# IOpins.net
KiCad netlist of a schematic drawn in Altium Designer
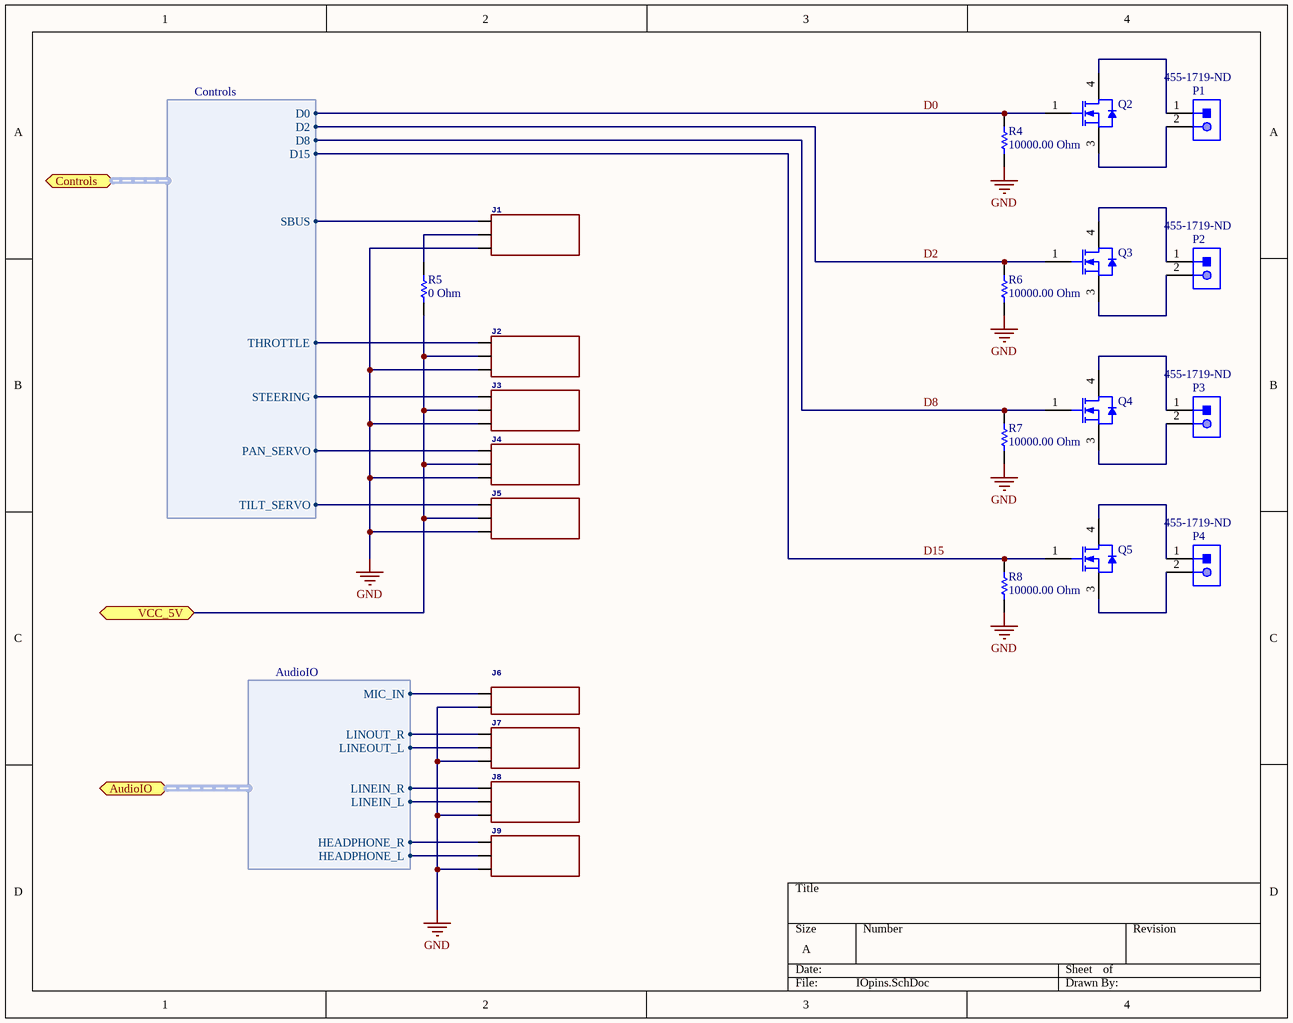
[diagram p0: IOpins.SchDoc]

(export (version "E")
  (design (tool "Eeschema 10.0.6"))
  (components
    (comp (ref "J1")
      (value "Library:  MF_Connectors Description: Header Connector with 03 Positions and 01 Rows. Use the LABEL Attribute to label the pin on the schematic and PCB. You can remove the attributes on the PCB by using the SMASH function on the part and then deleting the text.")
      (footprint "PTH_2.54MM_01X03")
      (fields (field (name "HOUSEPART") "YES") (field (name "MPN") "MF-CON-2.54mm-01x03"))
      (libsource (lib "MF_Connectors") (part "CON_01X03_PTH_2.54MM"))
    )
    (comp (ref "J2")
      (value "Library:  MF_Connectors Description: Header Connector with 03 Positions and 01 Rows. Use the LABEL Attribute to label the pin on the schematic and PCB. You can remove the attributes on the PCB by using the SMASH function on the part and then deleting the text.")
      (footprint "PTH_2.54MM_01X03")
      (fields (field (name "HOUSEPART") "YES") (field (name "MPN") "MF-CON-2.54mm-01x03"))
      (libsource (lib "MF_Connectors") (part "CON_01X03_PTH_2.54MM"))
    )
    (comp (ref "J3")
      (value "Library:  MF_Connectors Description: Header Connector with 03 Positions and 01 Rows. Use the LABEL Attribute to label the pin on the schematic and PCB. You can remove the attributes on the PCB by using the SMASH function on the part and then deleting the text.")
      (footprint "PTH_2.54MM_01X03")
      (fields (field (name "HOUSEPART") "YES") (field (name "MPN") "MF-CON-2.54mm-01x03"))
      (libsource (lib "MF_Connectors") (part "CON_01X03_PTH_2.54MM"))
    )
    (comp (ref "J4")
      (value "Library:  MF_Connectors Description: Header Connector with 03 Positions and 01 Rows. Use the LABEL Attribute to label the pin on the schematic and PCB. You can remove the attributes on the PCB by using the SMASH function on the part and then deleting the text.")
      (footprint "PTH_2.54MM_01X03")
      (fields (field (name "HOUSEPART") "YES") (field (name "MPN") "MF-CON-2.54mm-01x03"))
      (libsource (lib "MF_Connectors") (part "CON_01X03_PTH_2.54MM"))
    )
    (comp (ref "J5")
      (value "Library:  MF_Connectors Description: Header Connector with 03 Positions and 01 Rows. Use the LABEL Attribute to label the pin on the schematic and PCB. You can remove the attributes on the PCB by using the SMASH function on the part and then deleting the text.")
      (footprint "PTH_2.54MM_01X03")
      (fields (field (name "HOUSEPART") "YES") (field (name "MPN") "MF-CON-2.54mm-01x03"))
      (libsource (lib "MF_Connectors") (part "CON_01X03_PTH_2.54MM"))
    )
    (comp (ref "J6")
      (value "Library:  MF_Connectors Description: Header Connector with 02 Positions and 01 Rows. Use the LABEL Attribute to label the pin on the schematic and PCB. You can remove the attributes on the PCB by using the SMASH function on the part and then deleting the text.")
      (footprint "PTH_2.54MM_01X02")
      (fields (field (name "HOUSEPART") "YES") (field (name "MPN") "MF-CON-2.54mm-01x02"))
      (libsource (lib "MF_Connectors") (part "CON_01X02_PTH_2.54MM"))
    )
    (comp (ref "J7")
      (value "Library:  MF_Connectors Description: Header Connector with 03 Positions and 01 Rows. Use the LABEL Attribute to label the pin on the schematic and PCB. You can remove the attributes on the PCB by using the SMASH function on the part and then deleting the text.")
      (footprint "PTH_2.54MM_01X03")
      (fields (field (name "HOUSEPART") "YES") (field (name "MPN") "MF-CON-2.54mm-01x03"))
      (libsource (lib "MF_Connectors") (part "CON_01X03_PTH_2.54MM"))
    )
    (comp (ref "J8")
      (value "Library:  MF_Connectors Description: Header Connector with 03 Positions and 01 Rows. Use the LABEL Attribute to label the pin on the schematic and PCB. You can remove the attributes on the PCB by using the SMASH function on the part and then deleting the text.")
      (footprint "PTH_2.54MM_01X03")
      (fields (field (name "HOUSEPART") "YES") (field (name "MPN") "MF-CON-2.54mm-01x03"))
      (libsource (lib "MF_Connectors") (part "CON_01X03_PTH_2.54MM"))
    )
    (comp (ref "J9")
      (value "Library:  MF_Connectors Description: Header Connector with 03 Positions and 01 Rows. Use the LABEL Attribute to label the pin on the schematic and PCB. You can remove the attributes on the PCB by using the SMASH function on the part and then deleting the text.")
      (footprint "PTH_2.54MM_01X03")
      (fields (field (name "HOUSEPART") "YES") (field (name "MPN") "MF-CON-2.54mm-01x03"))
      (libsource (lib "MF_Connectors") (part "CON_01X03_PTH_2.54MM"))
    )
    (comp (ref "P1")
      (value "S2B-PH-K-S(LF)(SN)")
      (footprint "JST-S2B-PH-K-S_V")
      (fields (field (name "TOLERANCE") "20%") (field (name "SUPPLIER PART NUMBER 1") "455-1719-ND"))
      (libsource (lib "Altium Content Vault") (part "CMP-1755-00004-1"))
    )
    (comp (ref "P2")
      (value "S2B-PH-K-S(LF)(SN)")
      (footprint "JST-S2B-PH-K-S_V")
      (fields (field (name "TOLERANCE") "20%") (field (name "SUPPLIER PART NUMBER 1") "455-1719-ND"))
      (libsource (lib "Altium Content Vault") (part "CMP-1755-00004-1"))
    )
    (comp (ref "P3")
      (value "S2B-PH-K-S(LF)(SN)")
      (footprint "JST-S2B-PH-K-S_V")
      (fields (field (name "TOLERANCE") "20%") (field (name "SUPPLIER PART NUMBER 1") "455-1719-ND"))
      (libsource (lib "Altium Content Vault") (part "CMP-1755-00004-1"))
    )
    (comp (ref "P4")
      (value "S2B-PH-K-S(LF)(SN)")
      (footprint "JST-S2B-PH-K-S_V")
      (fields (field (name "TOLERANCE") "20%") (field (name "SUPPLIER PART NUMBER 1") "455-1719-ND"))
      (libsource (lib "Altium Content Vault") (part "CMP-1755-00004-1"))
    )
    (comp (ref "Q2")
      (value "NTD5867NLT4G")
      (footprint "ONSC-DPAK-3-369AA-01_V")
      (description "N-Channel Power MOSFET, 60 V, 20 A, 39 mOhm, 3-Pin DPAK, Pb-Free, Tape and Reel")
      (fields (field (name "MANUFACTURER") "On Semiconductor"))
      (libsource (lib "Altium Content Vault") (part "CMP-1058-00318-1"))
    )
    (comp (ref "Q3")
      (value "NTD5867NLT4G")
      (footprint "ONSC-DPAK-3-369AA-01_V")
      (description "N-Channel Power MOSFET, 60 V, 20 A, 39 mOhm, 3-Pin DPAK, Pb-Free, Tape and Reel")
      (fields (field (name "MANUFACTURER") "On Semiconductor"))
      (libsource (lib "Altium Content Vault") (part "CMP-1058-00318-1"))
    )
    (comp (ref "Q4")
      (value "NTD5867NLT4G")
      (footprint "ONSC-DPAK-3-369AA-01_V")
      (description "N-Channel Power MOSFET, 60 V, 20 A, 39 mOhm, 3-Pin DPAK, Pb-Free, Tape and Reel")
      (fields (field (name "MANUFACTURER") "On Semiconductor"))
      (libsource (lib "Altium Content Vault") (part "CMP-1058-00318-1"))
    )
    (comp (ref "Q5")
      (value "NTD5867NLT4G")
      (footprint "ONSC-DPAK-3-369AA-01_V")
      (description "N-Channel Power MOSFET, 60 V, 20 A, 39 mOhm, 3-Pin DPAK, Pb-Free, Tape and Reel")
      (fields (field (name "MANUFACTURER") "On Semiconductor"))
      (libsource (lib "Altium Content Vault") (part "CMP-1058-00318-1"))
    )
    (comp (ref "R4")
      (value "10000.00 Ohm")
      (footprint "RESC0402(1005)_N")
      (description "10K 0.063W 5% 0402 (1005 Metric)  SMD")
      (fields (field (name "POWER") "0.063 W") (field (name "TOLERANCE") "5 %"))
      (libsource (lib "Altium Content Vault") (part "CMP-1011-00081-1"))
    )
    (comp (ref "R5")
      (value "0 Ohm")
      (footprint "RESC0402(1005)_N")
      (description "10K 0.063W 5% 0402 (1005 Metric)  SMD")
      (fields (field (name "POWER") "0.063 W") (field (name "TOLERANCE") "5 %"))
      (libsource (lib "Altium Content Vault") (part "CMP-1011-00081-1"))
    )
    (comp (ref "R6")
      (value "10000.00 Ohm")
      (footprint "RESC0402(1005)_N")
      (description "10K 0.063W 5% 0402 (1005 Metric)  SMD")
      (fields (field (name "POWER") "0.063 W") (field (name "TOLERANCE") "5 %"))
      (libsource (lib "Altium Content Vault") (part "CMP-1011-00081-1"))
    )
    (comp (ref "R7")
      (value "10000.00 Ohm")
      (footprint "RESC0402(1005)_N")
      (description "10K 0.063W 5% 0402 (1005 Metric)  SMD")
      (fields (field (name "POWER") "0.063 W") (field (name "TOLERANCE") "5 %"))
      (libsource (lib "Altium Content Vault") (part "CMP-1011-00081-1"))
    )
    (comp (ref "R8")
      (value "10000.00 Ohm")
      (footprint "RESC0402(1005)_N")
      (description "10K 0.063W 5% 0402 (1005 Metric)  SMD")
      (fields (field (name "POWER") "0.063 W") (field (name "TOLERANCE") "5 %"))
      (libsource (lib "Altium Content Vault") (part "CMP-1011-00081-1"))
    )
  )
  (nets
    (net (code "3") (name "/D0") (class "Default")
      (node (ref "Q2") (pin "1") (pinfunction "G_1") (pintype "passive"))
      (node (ref "R4") (pin "2") (pinfunction "2_2") (pintype "passive"))
    )
    (net (code "4") (name "/D2") (class "Default")
      (node (ref "Q3") (pin "1") (pinfunction "G_1") (pintype "passive"))
      (node (ref "R6") (pin "2") (pinfunction "2_2") (pintype "passive"))
    )
    (net (code "5") (name "/D8") (class "Default")
      (node (ref "Q4") (pin "1") (pinfunction "G_1") (pintype "passive"))
      (node (ref "R7") (pin "2") (pinfunction "2_2") (pintype "passive"))
    )
    (net (code "6") (name "/D15") (class "Default")
      (node (ref "Q5") (pin "1") (pinfunction "G_1") (pintype "passive"))
      (node (ref "R8") (pin "2") (pinfunction "2_2") (pintype "passive"))
    )
    (net (code "7") (name "/HEADPHONE_L") (class "Default")
      (node (ref "J9") (pin "P$2") (pinfunction "PIN2_P$2") (pintype "passive"))
    )
    (net (code "8") (name "/HEADPHONE_R") (class "Default")
      (node (ref "J9") (pin "P$1") (pinfunction "PIN1_P$1") (pintype "passive"))
    )
    (net (code "9") (name "/LINEIN_L") (class "Default")
      (node (ref "J8") (pin "P$2") (pinfunction "PIN2_P$2") (pintype "passive"))
    )
    (net (code "10") (name "/LINEIN_R") (class "Default")
      (node (ref "J8") (pin "P$1") (pinfunction "PIN1_P$1") (pintype "passive"))
    )
    (net (code "11") (name "/LINEOUT_L") (class "Default")
      (node (ref "J7") (pin "P$2") (pinfunction "PIN2_P$2") (pintype "passive"))
    )
    (net (code "12") (name "/LINOUT_R") (class "Default")
      (node (ref "J7") (pin "P$1") (pinfunction "PIN1_P$1") (pintype "passive"))
    )
    (net (code "13") (name "/MIC_IN") (class "Default")
      (node (ref "J6") (pin "P$1") (pinfunction "PIN1_P$1") (pintype "passive"))
    )
    (net (code "14") (name "/PAN_SERVO") (class "Default")
      (node (ref "J4") (pin "P$1") (pinfunction "PIN1_P$1") (pintype "passive"))
    )
    (net (code "15") (name "/SBUS") (class "Default")
      (node (ref "J1") (pin "P$1") (pinfunction "PIN1_P$1") (pintype "passive"))
    )
    (net (code "16") (name "/STEERING") (class "Default")
      (node (ref "J3") (pin "P$1") (pinfunction "PIN1_P$1") (pintype "passive"))
    )
    (net (code "17") (name "/THROTTLE") (class "Default")
      (node (ref "J2") (pin "P$1") (pinfunction "PIN1_P$1") (pintype "passive"))
    )
    (net (code "18") (name "/TILT_SERVO") (class "Default")
      (node (ref "J5") (pin "P$1") (pinfunction "PIN1_P$1") (pintype "passive"))
    )
    (net (code "19") (name "/VCC_5V") (class "Default")
      (node (ref "J2") (pin "P$2") (pinfunction "PIN2_P$2") (pintype "passive"))
      (node (ref "J3") (pin "P$2") (pinfunction "PIN2_P$2") (pintype "passive"))
      (node (ref "J4") (pin "P$2") (pinfunction "PIN2_P$2") (pintype "passive"))
      (node (ref "J5") (pin "P$2") (pinfunction "PIN2_P$2") (pintype "passive"))
      (node (ref "R5") (pin "1") (pinfunction "1_1") (pintype "passive"))
    )
    (net (code "22") (name "GND") (class "Default")
      (node (ref "J1") (pin "P$3") (pinfunction "PIN3_P$3") (pintype "passive"))
      (node (ref "J2") (pin "P$3") (pinfunction "PIN3_P$3") (pintype "passive"))
      (node (ref "J3") (pin "P$3") (pinfunction "PIN3_P$3") (pintype "passive"))
      (node (ref "J4") (pin "P$3") (pinfunction "PIN3_P$3") (pintype "passive"))
      (node (ref "J5") (pin "P$3") (pinfunction "PIN3_P$3") (pintype "passive"))
      (node (ref "J6") (pin "P$2") (pinfunction "PIN2_P$2") (pintype "passive"))
      (node (ref "J7") (pin "P$3") (pinfunction "PIN3_P$3") (pintype "passive"))
      (node (ref "J8") (pin "P$3") (pinfunction "PIN3_P$3") (pintype "passive"))
      (node (ref "J9") (pin "P$3") (pinfunction "PIN3_P$3") (pintype "passive"))
      (node (ref "R4") (pin "1") (pinfunction "1_1") (pintype "passive"))
      (node (ref "R6") (pin "1") (pinfunction "1_1") (pintype "passive"))
      (node (ref "R7") (pin "1") (pinfunction "1_1") (pintype "passive"))
      (node (ref "R8") (pin "1") (pinfunction "1_1") (pintype "passive"))
    )
    (net (code "23") (name "Net-(J1-PIN2)") (class "Default")
      (node (ref "J1") (pin "P$2") (pinfunction "PIN2_P$2") (pintype "passive"))
      (node (ref "R5") (pin "2") (pinfunction "2_2") (pintype "passive"))
    )
    (net (code "24") (name "Net-(Q2-D)") (class "Default")
      (node (ref "P1") (pin "1") (pinfunction "1_1") (pintype "passive"))
      (node (ref "Q2") (pin "4") (pinfunction "D_4") (pintype "passive"))
    )
    (net (code "25") (name "Net-(Q2-S)") (class "Default")
      (node (ref "P1") (pin "2") (pinfunction "2_2") (pintype "passive"))
      (node (ref "Q2") (pin "3") (pinfunction "S_3") (pintype "passive"))
    )
    (net (code "26") (name "Net-(Q3-D)") (class "Default")
      (node (ref "P2") (pin "1") (pinfunction "1_1") (pintype "passive"))
      (node (ref "Q3") (pin "4") (pinfunction "D_4") (pintype "passive"))
    )
    (net (code "27") (name "Net-(Q3-S)") (class "Default")
      (node (ref "P2") (pin "2") (pinfunction "2_2") (pintype "passive"))
      (node (ref "Q3") (pin "3") (pinfunction "S_3") (pintype "passive"))
    )
    (net (code "28") (name "Net-(Q4-D)") (class "Default")
      (node (ref "P3") (pin "1") (pinfunction "1_1") (pintype "passive"))
      (node (ref "Q4") (pin "4") (pinfunction "D_4") (pintype "passive"))
    )
    (net (code "29") (name "Net-(Q4-S)") (class "Default")
      (node (ref "P3") (pin "2") (pinfunction "2_2") (pintype "passive"))
      (node (ref "Q4") (pin "3") (pinfunction "S_3") (pintype "passive"))
    )
    (net (code "30") (name "Net-(Q5-D)") (class "Default")
      (node (ref "P4") (pin "1") (pinfunction "1_1") (pintype "passive"))
      (node (ref "Q5") (pin "4") (pinfunction "D_4") (pintype "passive"))
    )
    (net (code "31") (name "Net-(Q5-S)") (class "Default")
      (node (ref "P4") (pin "2") (pinfunction "2_2") (pintype "passive"))
      (node (ref "Q5") (pin "3") (pinfunction "S_3") (pintype "passive"))
    )
  )
)
